# DAC_board_schematic.net
KiCad netlist of a schematic drawn in Altium Designer
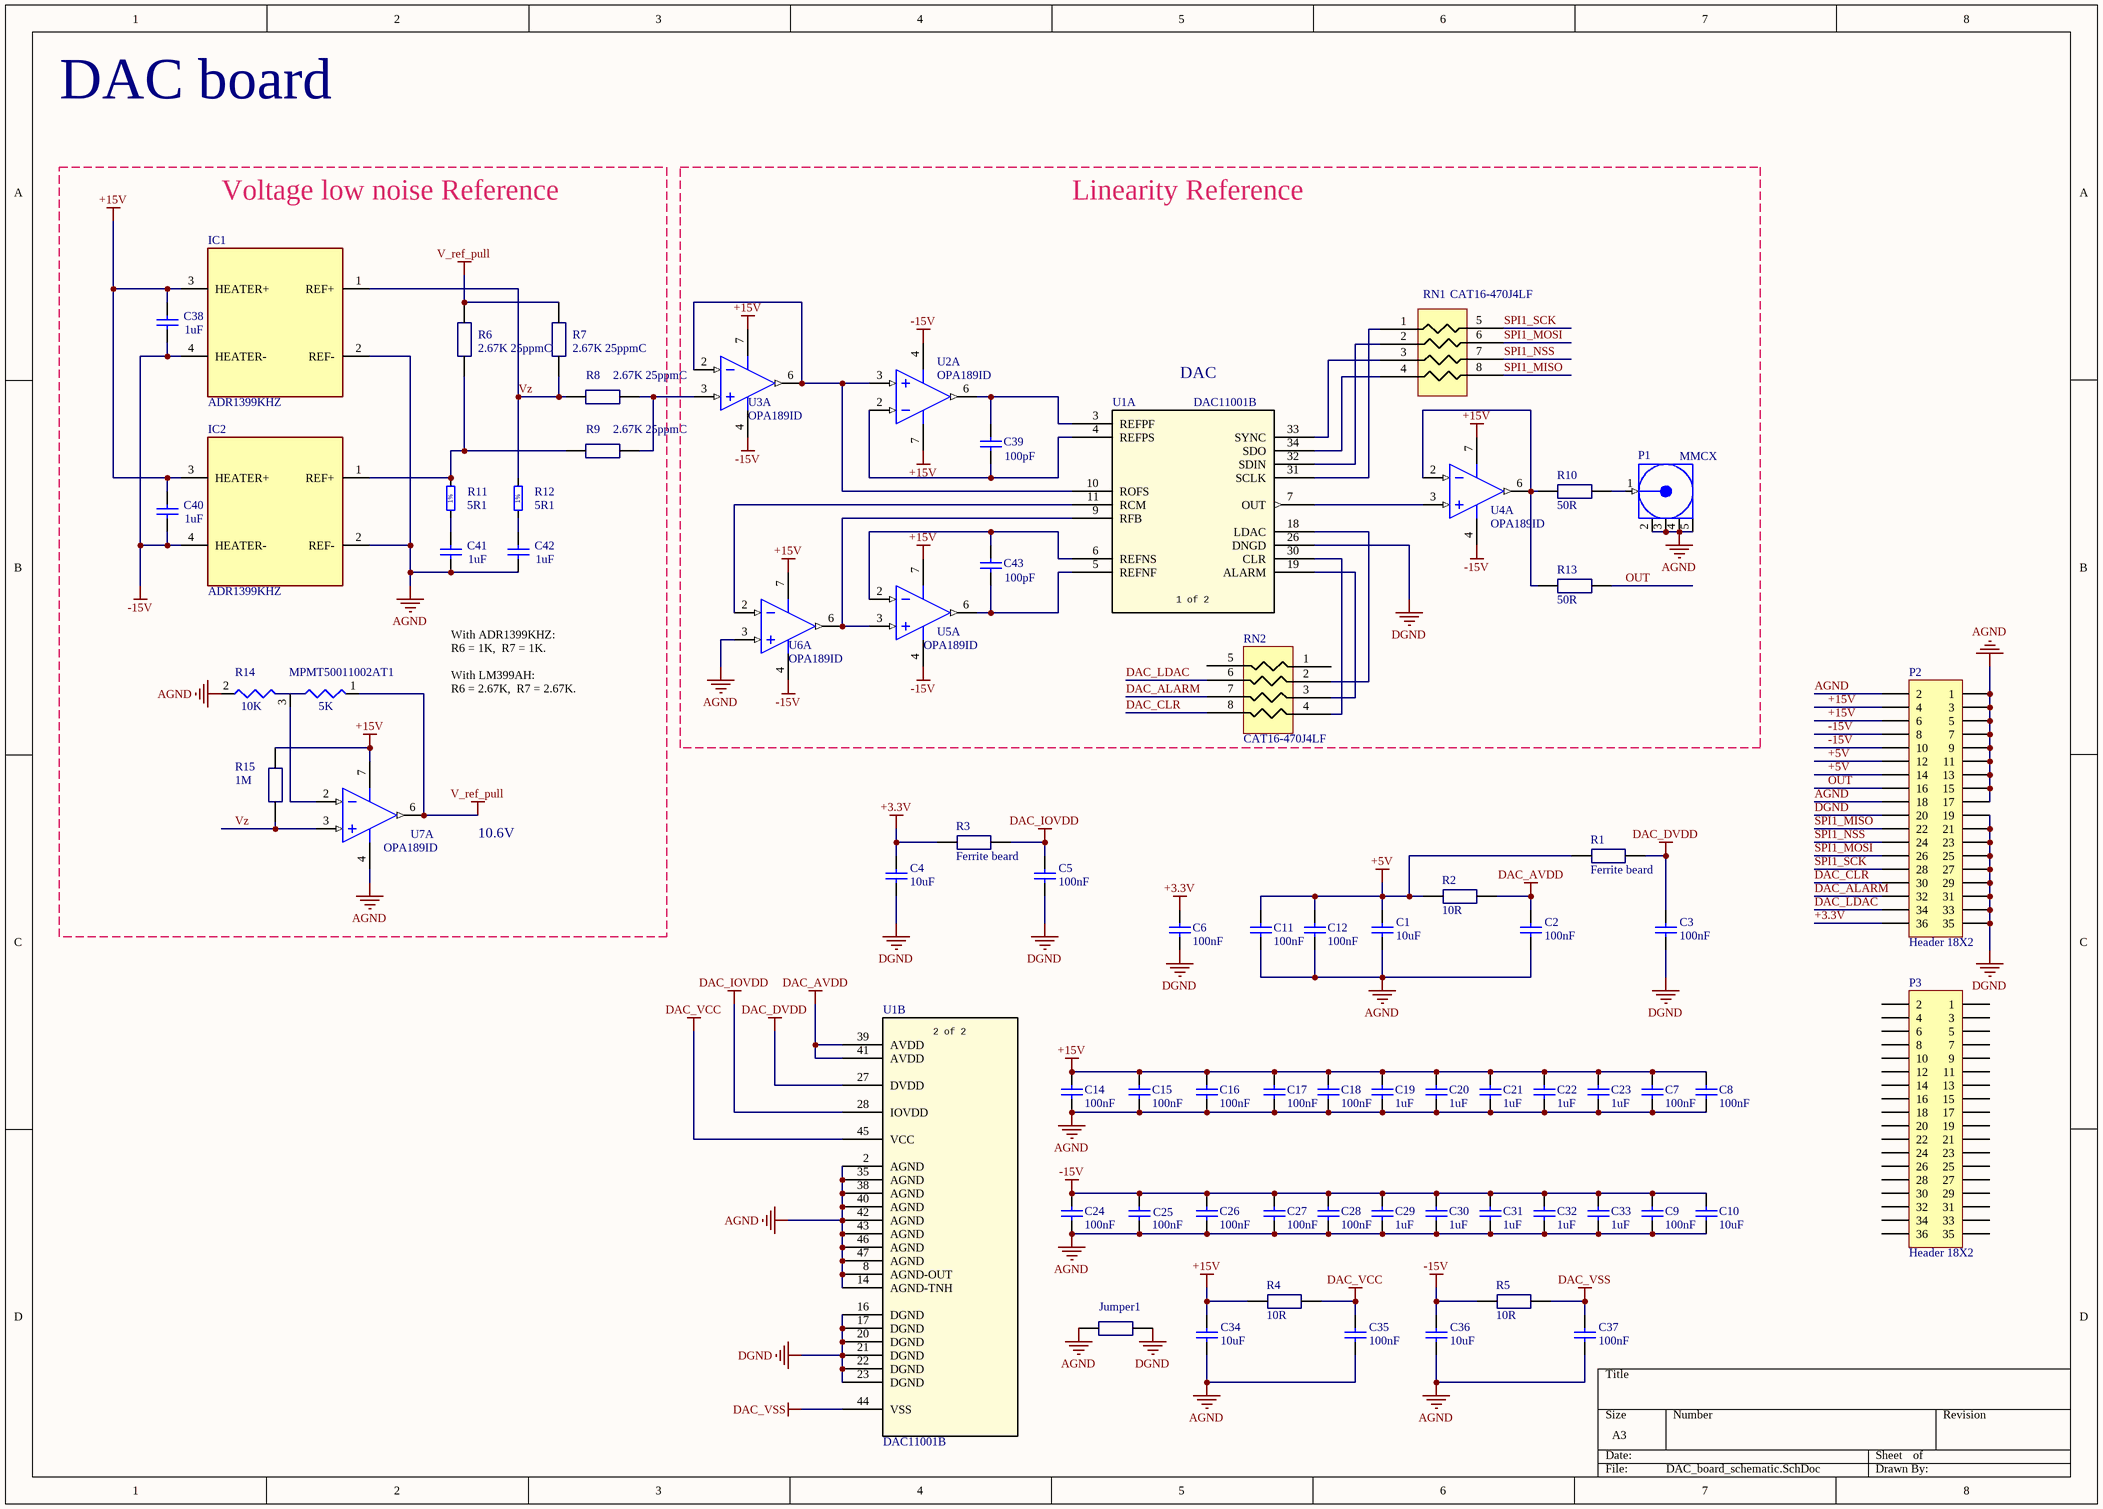
[diagram p0: DAC_board_schematic.SchDoc]

(export (version "E")
  (design (tool "Eeschema 10.0.6"))
  (components
    (comp (ref "C1")
      (value "10uF")
      (footprint "CAP 0603")
      (description "Capacitor (Semiconductor SIM Model)")
      (fields (field (name "PUBLISHER") "Altium Limited"))
      (libsource (lib "Miscellaneous Devices") (part "Cap Semi"))
    )
    (comp (ref "C2")
      (value "100nF")
      (footprint "CAP 0603")
      (description "Capacitor (Semiconductor SIM Model)")
      (fields (field (name "PUBLISHER") "Altium Limited"))
      (libsource (lib "Miscellaneous Devices") (part "Cap Semi"))
    )
    (comp (ref "C3")
      (value "100nF")
      (footprint "CAP 0603")
      (description "Capacitor (Semiconductor SIM Model)")
      (fields (field (name "PUBLISHER") "Altium Limited"))
      (libsource (lib "Miscellaneous Devices") (part "Cap Semi"))
    )
    (comp (ref "C4")
      (value "10uF")
      (footprint "CAP 0603")
      (description "Capacitor (Semiconductor SIM Model)")
      (fields (field (name "PUBLISHER") "Altium Limited"))
      (libsource (lib "Miscellaneous Devices") (part "Cap Semi"))
    )
    (comp (ref "C5")
      (value "100nF")
      (footprint "CAP 0603")
      (description "Capacitor (Semiconductor SIM Model)")
      (fields (field (name "PUBLISHER") "Altium Limited"))
      (libsource (lib "Miscellaneous Devices") (part "Cap Semi"))
    )
    (comp (ref "C6")
      (value "100nF")
      (footprint "CAP 0603")
      (description "Capacitor (Semiconductor SIM Model)")
      (fields (field (name "PUBLISHER") "Altium Limited"))
      (libsource (lib "Miscellaneous Devices") (part "Cap Semi"))
    )
    (comp (ref "C7")
      (value "100nF")
      (footprint "CAP 0603")
      (description "Capacitor (Semiconductor SIM Model)")
      (fields (field (name "PUBLISHER") "Altium Limited"))
      (libsource (lib "Miscellaneous Devices") (part "Cap Semi"))
    )
    (comp (ref "C8")
      (value "100nF")
      (footprint "CAP 0603")
      (description "Capacitor (Semiconductor SIM Model)")
      (fields (field (name "PUBLISHER") "Altium Limited"))
      (libsource (lib "Miscellaneous Devices") (part "Cap Semi"))
    )
    (comp (ref "C9")
      (value "100nF")
      (footprint "CAP 0603")
      (description "Capacitor (Semiconductor SIM Model)")
      (fields (field (name "PUBLISHER") "Altium Limited"))
      (libsource (lib "Miscellaneous Devices") (part "Cap Semi"))
    )
    (comp (ref "C10")
      (value "10uF")
      (footprint "CAP 0603")
      (description "Capacitor (Semiconductor SIM Model)")
      (fields (field (name "PUBLISHER") "Altium Limited"))
      (libsource (lib "Miscellaneous Devices") (part "Cap Semi"))
    )
    (comp (ref "C11")
      (value "100nF")
      (footprint "CAP 0603")
      (description "Capacitor (Semiconductor SIM Model)")
      (fields (field (name "PUBLISHER") "Altium Limited"))
      (libsource (lib "Miscellaneous Devices") (part "Cap Semi"))
    )
    (comp (ref "C12")
      (value "100nF")
      (footprint "CAP 0603")
      (description "Capacitor (Semiconductor SIM Model)")
      (fields (field (name "PUBLISHER") "Altium Limited"))
      (libsource (lib "Miscellaneous Devices") (part "Cap Semi"))
    )
    (comp (ref "C14")
      (value "100nF")
      (footprint "CAP 0603")
      (description "Capacitor (Semiconductor SIM Model)")
      (fields (field (name "PUBLISHER") "Altium Limited"))
      (libsource (lib "Miscellaneous Devices") (part "Cap Semi"))
    )
    (comp (ref "C15")
      (value "100nF")
      (footprint "CAP 0603")
      (description "Capacitor (Semiconductor SIM Model)")
      (fields (field (name "PUBLISHER") "Altium Limited"))
      (libsource (lib "Miscellaneous Devices") (part "Cap Semi"))
    )
    (comp (ref "C16")
      (value "100nF")
      (footprint "CAP 0603")
      (description "Capacitor (Semiconductor SIM Model)")
      (fields (field (name "PUBLISHER") "Altium Limited"))
      (libsource (lib "Miscellaneous Devices") (part "Cap Semi"))
    )
    (comp (ref "C17")
      (value "100nF")
      (footprint "CAP 0603")
      (description "Capacitor (Semiconductor SIM Model)")
      (fields (field (name "PUBLISHER") "Altium Limited"))
      (libsource (lib "Miscellaneous Devices") (part "Cap Semi"))
    )
    (comp (ref "C18")
      (value "100nF")
      (footprint "CAP 0603")
      (description "Capacitor (Semiconductor SIM Model)")
      (fields (field (name "PUBLISHER") "Altium Limited"))
      (libsource (lib "Miscellaneous Devices") (part "Cap Semi"))
    )
    (comp (ref "C19")
      (value "1uF")
      (footprint "CAP 0603")
      (description "Capacitor (Semiconductor SIM Model)")
      (fields (field (name "PUBLISHER") "Altium Limited"))
      (libsource (lib "Miscellaneous Devices") (part "Cap Semi"))
    )
    (comp (ref "C20")
      (value "1uF")
      (footprint "CAP 0603")
      (description "Capacitor (Semiconductor SIM Model)")
      (fields (field (name "PUBLISHER") "Altium Limited"))
      (libsource (lib "Miscellaneous Devices") (part "Cap Semi"))
    )
    (comp (ref "C21")
      (value "1uF")
      (footprint "CAP 0603")
      (description "Capacitor (Semiconductor SIM Model)")
      (fields (field (name "PUBLISHER") "Altium Limited"))
      (libsource (lib "Miscellaneous Devices") (part "Cap Semi"))
    )
    (comp (ref "C22")
      (value "1uF")
      (footprint "CAP 0603")
      (description "Capacitor (Semiconductor SIM Model)")
      (fields (field (name "PUBLISHER") "Altium Limited"))
      (libsource (lib "Miscellaneous Devices") (part "Cap Semi"))
    )
    (comp (ref "C23")
      (value "1uF")
      (footprint "CAP 0603")
      (description "Capacitor (Semiconductor SIM Model)")
      (fields (field (name "PUBLISHER") "Altium Limited"))
      (libsource (lib "Miscellaneous Devices") (part "Cap Semi"))
    )
    (comp (ref "C24")
      (value "100nF")
      (footprint "CAP 0603")
      (description "Capacitor (Semiconductor SIM Model)")
      (fields (field (name "PUBLISHER") "Altium Limited"))
      (libsource (lib "Miscellaneous Devices") (part "Cap Semi"))
    )
    (comp (ref "C25")
      (value "100nF")
      (footprint "CAP 0603")
      (description "Capacitor (Semiconductor SIM Model)")
      (fields (field (name "PUBLISHER") "Altium Limited"))
      (libsource (lib "Miscellaneous Devices") (part "Cap Semi"))
    )
    (comp (ref "C26")
      (value "100nF")
      (footprint "CAP 0603")
      (description "Capacitor (Semiconductor SIM Model)")
      (fields (field (name "PUBLISHER") "Altium Limited"))
      (libsource (lib "Miscellaneous Devices") (part "Cap Semi"))
    )
    (comp (ref "C27")
      (value "100nF")
      (footprint "CAP 0603")
      (description "Capacitor (Semiconductor SIM Model)")
      (fields (field (name "PUBLISHER") "Altium Limited"))
      (libsource (lib "Miscellaneous Devices") (part "Cap Semi"))
    )
    (comp (ref "C28")
      (value "100nF")
      (footprint "CAP 0603")
      (description "Capacitor (Semiconductor SIM Model)")
      (fields (field (name "PUBLISHER") "Altium Limited"))
      (libsource (lib "Miscellaneous Devices") (part "Cap Semi"))
    )
    (comp (ref "C29")
      (value "1uF")
      (footprint "CAP 0603")
      (description "Capacitor (Semiconductor SIM Model)")
      (fields (field (name "PUBLISHER") "Altium Limited"))
      (libsource (lib "Miscellaneous Devices") (part "Cap Semi"))
    )
    (comp (ref "C30")
      (value "1uF")
      (footprint "CAP 0603")
      (description "Capacitor (Semiconductor SIM Model)")
      (fields (field (name "PUBLISHER") "Altium Limited"))
      (libsource (lib "Miscellaneous Devices") (part "Cap Semi"))
    )
    (comp (ref "C31")
      (value "1uF")
      (footprint "CAP 0603")
      (description "Capacitor (Semiconductor SIM Model)")
      (fields (field (name "PUBLISHER") "Altium Limited"))
      (libsource (lib "Miscellaneous Devices") (part "Cap Semi"))
    )
    (comp (ref "C32")
      (value "1uF")
      (footprint "CAP 0603")
      (description "Capacitor (Semiconductor SIM Model)")
      (fields (field (name "PUBLISHER") "Altium Limited"))
      (libsource (lib "Miscellaneous Devices") (part "Cap Semi"))
    )
    (comp (ref "C33")
      (value "1uF")
      (footprint "CAP 0603")
      (description "Capacitor (Semiconductor SIM Model)")
      (fields (field (name "PUBLISHER") "Altium Limited"))
      (libsource (lib "Miscellaneous Devices") (part "Cap Semi"))
    )
    (comp (ref "C34")
      (value "10uF")
      (footprint "C1206")
      (description "Capacitor (Semiconductor SIM Model)")
      (fields (field (name "PUBLISHER") "Altium Limited"))
      (libsource (lib "Miscellaneous Devices") (part "Cap Semi"))
    )
    (comp (ref "C35")
      (value "100nF")
      (footprint "CAP 0603")
      (description "Capacitor (Semiconductor SIM Model)")
      (fields (field (name "PUBLISHER") "Altium Limited"))
      (libsource (lib "Miscellaneous Devices") (part "Cap Semi"))
    )
    (comp (ref "C36")
      (value "10uF")
      (footprint "C1206")
      (description "Capacitor (Semiconductor SIM Model)")
      (fields (field (name "PUBLISHER") "Altium Limited"))
      (libsource (lib "Miscellaneous Devices") (part "Cap Semi"))
    )
    (comp (ref "C37")
      (value "100nF")
      (footprint "CAP 0603")
      (description "Capacitor (Semiconductor SIM Model)")
      (fields (field (name "PUBLISHER") "Altium Limited"))
      (libsource (lib "Miscellaneous Devices") (part "Cap Semi"))
    )
    (comp (ref "C38")
      (value "1uF")
      (footprint "CAPC3216X140N")
      (description "Non-polarised capacitor")
      (fields
        (field (name "PART NUMBER") "CC1206_1UF_25V_10%_X7R")
        (field (name "VOLTAGE") "25V")
        (field (name "AUTHOR") "CERN DEM JLC")
      )
      (libsource (lib "Capacitors") (part "Capacitor - non polarized"))
    )
    (comp (ref "C39")
      (value "100pF")
      (footprint "0402")
      (description "Capacitor (Semiconductor SIM Model)")
      (fields (field (name "Comment") "Cap Semi") (field (name "PUBLISHER") "Altium Limited"))
      (libsource (lib "Miscellaneous Devices") (part "Cap Semi"))
    )
    (comp (ref "C40")
      (value "1uF")
      (footprint "CAPC3216X140N")
      (description "Non-polarised capacitor")
      (fields
        (field (name "PART NUMBER") "CC1206_1UF_25V_10%_X7R")
        (field (name "VOLTAGE") "25V")
        (field (name "AUTHOR") "CERN DEM JLC")
      )
      (libsource (lib "Capacitors") (part "Capacitor - non polarized"))
    )
    (comp (ref "C41")
      (value "1uF")
      (footprint "CAPC3216X140N")
      (description "Non-polarised capacitor")
      (fields
        (field (name "PART NUMBER") "CC1206_1UF_25V_10%_X7R")
        (field (name "VOLTAGE") "25V")
        (field (name "AUTHOR") "CERN DEM JLC")
      )
      (libsource (lib "Capacitors") (part "Capacitor - non polarized"))
    )
    (comp (ref "C42")
      (value "1uF")
      (footprint "CAPC3216X140N")
      (description "Non-polarised capacitor")
      (fields
        (field (name "PART NUMBER") "CC1206_1UF_25V_10%_X7R")
        (field (name "VOLTAGE") "25V")
        (field (name "AUTHOR") "CERN DEM JLC")
      )
      (libsource (lib "Capacitors") (part "Capacitor - non polarized"))
    )
    (comp (ref "C43")
      (value "100pF")
      (footprint "0402")
      (description "Capacitor (Semiconductor SIM Model)")
      (fields (field (name "Comment") "Cap Semi") (field (name "PUBLISHER") "Altium Limited"))
      (libsource (lib "Miscellaneous Devices") (part "Cap Semi"))
    )
    (comp (ref "IC1")
      (value "ADR1399KHZ")
      (footprint "SamacSys:ADR1399KHZ")
      (description "Integrated Circuit")
      (libsource (lib "SamacSys") (part "ADR1399KHZ"))
    )
    (comp (ref "IC2")
      (value "ADR1399KHZ")
      (footprint "SamacSys:ADR1399KHZ")
      (description "Integrated Circuit")
      (libsource (lib "SamacSys") (part "ADR1399KHZ"))
    )
    (comp (ref "Jumper1")
      (value "~")
      (footprint "0402 jumper")
      (libsource (lib "Микрон-3") (part "Resistor 0805"))
    )
    (comp (ref "P1")
      (value "MMCX")
      (footprint "MMCX2.54-V5")
      (description "RF Coaxial PCB Connector, MMCX; Thru-Hole, Vertical Mount Plug,  50 Ohm Impedance")
      (fields (field (name "PUBLISHER") "Altium Limited"))
      (libsource (lib "Miscellaneous Connectors") (part "COAX-M"))
    )
    (comp (ref "P2")
      (value "Header 18X2")
      (footprint "HDR2X18")
      (description "Header, 18-Pin, Dual row")
      (fields (field (name "PUBLISHER") "Altium Limited"))
      (libsource (lib "Miscellaneous Connectors") (part "Header 18X2"))
    )
    (comp (ref "P3")
      (value "Header 18X2")
      (footprint "HDR2X18")
      (description "Header, 18-Pin, Dual row")
      (fields (field (name "PUBLISHER") "Altium Limited"))
      (libsource (lib "Miscellaneous Connectors") (part "Header 18X2"))
    )
    (comp (ref "R1")
      (value "Ferrite beard")
      (footprint "CC1206JRNPOBBN100")
      (libsource (lib "Микрон-3") (part "Resistor 0805"))
    )
    (comp (ref "R2")
      (value "10R")
      (footprint "1608[0603]")
      (libsource (lib "Микрон-3") (part "Resistor 0805"))
    )
    (comp (ref "R3")
      (value "Ferrite beard")
      (footprint "CC1206JRNPOBBN100")
      (libsource (lib "Микрон-3") (part "Resistor 0805"))
    )
    (comp (ref "R4")
      (value "10R")
      (footprint "1608[0603]")
      (libsource (lib "Микрон-3") (part "Resistor 0805"))
    )
    (comp (ref "R5")
      (value "10R")
      (footprint "1608[0603]")
      (libsource (lib "Микрон-3") (part "Resistor 0805"))
    )
    (comp (ref "R6")
      (value "2.67K 25ppmC")
      (footprint "1608[0603]")
      (libsource (lib "Микрон-3") (part "Resistor 0805"))
    )
    (comp (ref "R7")
      (value "2.67K 25ppmC")
      (footprint "1608[0603]")
      (libsource (lib "Микрон-3") (part "Resistor 0805"))
    )
    (comp (ref "R8")
      (value "2.67K 25ppmC")
      (footprint "1608[0603]")
      (libsource (lib "Микрон-3") (part "Resistor 0805"))
    )
    (comp (ref "R9")
      (value "2.67K 25ppmC")
      (footprint "1608[0603]")
      (libsource (lib "Микрон-3") (part "Resistor 0805"))
    )
    (comp (ref "R10")
      (value "50R")
      (footprint "1608[0603]")
      (libsource (lib "Микрон-3") (part "Resistor 0805"))
    )
    (comp (ref "R11")
      (value "5R1")
      (footprint "RESC3216X65N")
      (description "Resistor - 1%")
      (fields
        (field (name "PART NUMBER") "R1206_5R6_1%_0.25W_200PPM")
        (field (name "POWER") "0.25W")
        (field (name "AUTHOR") "CERN DEM JLC")
      )
      (libsource (lib "Resistors") (part "Resistor - 1%"))
    )
    (comp (ref "R12")
      (value "5R1")
      (footprint "RESC3216X65N")
      (description "Resistor - 1%")
      (fields
        (field (name "PART NUMBER") "R1206_5R6_1%_0.25W_200PPM")
        (field (name "POWER") "0.25W")
        (field (name "AUTHOR") "CERN DEM JLC")
      )
      (libsource (lib "Resistors") (part "Resistor - 1%"))
    )
    (comp (ref "R13")
      (value "50R")
      (footprint "1608[0603]")
      (libsource (lib "Микрон-3") (part "Resistor 0805"))
    )
    (comp (ref "R14")
      (value "5K")
      (footprint "SOT23-3")
      (fields
        (field (name "VALUE2") "10K")
        (field (name "ORDER") "MPMT50011002AT1")
        (field (name "Comment") "MPMT50011002AT1")
        (field (name "PUBLISHER") "Altium Limited")
      )
      (libsource (lib "My SCH library") (part "MPMT"))
    )
    (comp (ref "R15")
      (value "1M")
      (footprint "1608[0603]")
      (libsource (lib "Микрон-3") (part "Resistor 0805"))
    )
    (comp (ref "RN1")
      (value "CAT16-470J4LF")
      (footprint "CAT16-470J4LF")
      (libsource (lib "My SCH library") (part "CAT16-470J4LF"))
    )
    (comp (ref "RN2")
      (value "CAT16-470J4LF")
      (footprint "CAT16-470J4LF")
      (libsource (lib "") (part "CAT16-470J4LF_1"))
    )
    (comp (ref "U1")
      (value "DAC11001B")
      (footprint "QFP_APFBR_TEX")
      (description "No Description Available")
      (fields
        (field (name "MANUFACTURER_PART_NUMBER") "DAC11001APFBR")
        (field (name "COPYRIGHT") "Copyright (C) 2018 Accelerated Designs. All rights reserved")
      )
      (libsource (lib "Ramp-generator") (part "DAC11001APFBR"))
    )
    (comp (ref "U2")
      (value "OPA189ID")
      (footprint "TI-D8_L")
      (fields (field (name "MANUFACTURER") "Texas Instruments"))
      (libsource (lib "") (part "OPA140AIDR_1"))
    )
    (comp (ref "U3")
      (value "OPA189ID")
      (footprint "TI-D8_L")
      (fields (field (name "MANUFACTURER") "Texas Instruments"))
      (libsource (lib "TI Amplifiers and Linear Operational Amplifier Precision Amplifier Part One") (part "OPA140AIDR"))
    )
    (comp (ref "U4")
      (value "OPA189ID")
      (footprint "TI-D8_L")
      (fields (field (name "MANUFACTURER") "Texas Instruments"))
      (libsource (lib "TI Amplifiers and Linear Operational Amplifier Precision Amplifier Part One") (part "OPA140AIDR"))
    )
    (comp (ref "U5")
      (value "OPA189ID")
      (footprint "TI-D8_L")
      (fields (field (name "MANUFACTURER") "Texas Instruments"))
      (libsource (lib "TI Amplifiers and Linear Operational Amplifier Precision Amplifier Part One") (part "OPA140AIDR"))
    )
    (comp (ref "U6")
      (value "OPA189ID")
      (footprint "TI-D8_L")
      (fields (field (name "MANUFACTURER") "Texas Instruments"))
      (libsource (lib "TI Amplifiers and Linear Operational Amplifier Precision Amplifier Part One") (part "OPA140AIDR"))
    )
    (comp (ref "U7")
      (value "OPA189ID")
      (footprint "TI-D8_L")
      (fields (field (name "MANUFACTURER") "Texas Instruments"))
      (libsource (lib "TI Amplifiers and Linear Operational Amplifier Precision Amplifier Part One") (part "OPA140AIDR"))
    )
  )
  (nets
    (net (code "1") (name "+3.3V") (class "Default")
      (node (ref "C4") (pin "1") (pinfunction "1_1") (pintype "passive"))
      (node (ref "C6") (pin "2") (pinfunction "2_2") (pintype "passive"))
      (node (ref "P2") (pin "36") (pinfunction "36_36") (pintype "passive"))
      (node (ref "R3") (pin "2") (pinfunction "2_2") (pintype "passive"))
    )
    (net (code "2") (name "+5V") (class "Default")
      (node (ref "C1") (pin "1") (pinfunction "1_1") (pintype "passive"))
      (node (ref "C11") (pin "2") (pinfunction "2_2") (pintype "passive"))
      (node (ref "C12") (pin "2") (pinfunction "2_2") (pintype "passive"))
      (node (ref "P2") (pin "12") (pinfunction "12_12") (pintype "passive"))
      (node (ref "P2") (pin "14") (pinfunction "14_14") (pintype "passive"))
      (node (ref "R1") (pin "2") (pinfunction "2_2") (pintype "passive"))
      (node (ref "R2") (pin "2") (pinfunction "2_2") (pintype "passive"))
    )
    (net (code "3") (name "+15V") (class "Default")
      (node (ref "C14") (pin "2") (pinfunction "2_2") (pintype "passive"))
      (node (ref "C15") (pin "2") (pinfunction "2_2") (pintype "passive"))
      (node (ref "C16") (pin "2") (pinfunction "2_2") (pintype "passive"))
      (node (ref "C17") (pin "2") (pinfunction "2_2") (pintype "passive"))
      (node (ref "C18") (pin "2") (pinfunction "2_2") (pintype "passive"))
      (node (ref "C19") (pin "2") (pinfunction "2_2") (pintype "passive"))
      (node (ref "C20") (pin "2") (pinfunction "2_2") (pintype "passive"))
      (node (ref "C21") (pin "2") (pinfunction "2_2") (pintype "passive"))
      (node (ref "C22") (pin "2") (pinfunction "2_2") (pintype "passive"))
      (node (ref "C23") (pin "2") (pinfunction "2_2") (pintype "passive"))
      (node (ref "C34") (pin "1") (pinfunction "1_1") (pintype "passive"))
      (node (ref "C38") (pin "2") (pinfunction "2_2") (pintype "passive"))
      (node (ref "C40") (pin "2") (pinfunction "2_2") (pintype "passive"))
      (node (ref "C7") (pin "2") (pinfunction "2_2") (pintype "passive"))
      (node (ref "C8") (pin "2") (pinfunction "2_2") (pintype "passive"))
      (node (ref "IC1") (pin "3") (pinfunction "HEATER+_3") (pintype "passive"))
      (node (ref "IC2") (pin "3") (pinfunction "HEATER+_3") (pintype "passive"))
      (node (ref "P2") (pin "4") (pinfunction "4_4") (pintype "passive"))
      (node (ref "P2") (pin "6") (pinfunction "6_6") (pintype "passive"))
      (node (ref "R15") (pin "1") (pinfunction "A_1") (pintype "passive"))
      (node (ref "R4") (pin "2") (pinfunction "2_2") (pintype "passive"))
      (node (ref "U2") (pin "7") (pinfunction "V+_7") (pintype "power_in"))
      (node (ref "U3") (pin "7") (pinfunction "V+_7") (pintype "power_in"))
      (node (ref "U4") (pin "7") (pinfunction "V+_7") (pintype "power_in"))
      (node (ref "U5") (pin "7") (pinfunction "V+_7") (pintype "power_in"))
      (node (ref "U6") (pin "7") (pinfunction "V+_7") (pintype "power_in"))
      (node (ref "U7") (pin "7") (pinfunction "V+_7") (pintype "power_in"))
    )
    (net (code "4") (name "-15V") (class "Default")
      (node (ref "C10") (pin "2") (pinfunction "2_2") (pintype "passive"))
      (node (ref "C24") (pin "2") (pinfunction "2_2") (pintype "passive"))
      (node (ref "C25") (pin "2") (pinfunction "2_2") (pintype "passive"))
      (node (ref "C26") (pin "2") (pinfunction "2_2") (pintype "passive"))
      (node (ref "C27") (pin "2") (pinfunction "2_2") (pintype "passive"))
      (node (ref "C28") (pin "2") (pinfunction "2_2") (pintype "passive"))
      (node (ref "C29") (pin "2") (pinfunction "2_2") (pintype "passive"))
      (node (ref "C30") (pin "2") (pinfunction "2_2") (pintype "passive"))
      (node (ref "C31") (pin "2") (pinfunction "2_2") (pintype "passive"))
      (node (ref "C32") (pin "2") (pinfunction "2_2") (pintype "passive"))
      (node (ref "C33") (pin "2") (pinfunction "2_2") (pintype "passive"))
      (node (ref "C36") (pin "1") (pinfunction "1_1") (pintype "passive"))
      (node (ref "C38") (pin "1") (pinfunction "1_1") (pintype "passive"))
      (node (ref "C40") (pin "1") (pinfunction "1_1") (pintype "passive"))
      (node (ref "C9") (pin "2") (pinfunction "2_2") (pintype "passive"))
      (node (ref "IC1") (pin "4") (pinfunction "HEATER-_4") (pintype "passive"))
      (node (ref "IC2") (pin "4") (pinfunction "HEATER-_4") (pintype "passive"))
      (node (ref "P2") (pin "10") (pinfunction "10_10") (pintype "passive"))
      (node (ref "P2") (pin "8") (pinfunction "8_8") (pintype "passive"))
      (node (ref "R5") (pin "2") (pinfunction "2_2") (pintype "passive"))
      (node (ref "U2") (pin "4") (pinfunction "V-_4") (pintype "power_in"))
      (node (ref "U3") (pin "4") (pinfunction "V-_4") (pintype "power_in"))
      (node (ref "U4") (pin "4") (pinfunction "V-_4") (pintype "power_in"))
      (node (ref "U5") (pin "4") (pinfunction "V-_4") (pintype "power_in"))
      (node (ref "U6") (pin "4") (pinfunction "V-_4") (pintype "power_in"))
    )
    (net (code "5") (name "/DAC_ALARM") (class "Default")
      (node (ref "P2") (pin "32") (pinfunction "32_32") (pintype "passive"))
      (node (ref "RN2") (pin "7") (pinfunction "7_7") (pintype "passive"))
    )
    (net (code "6") (name "/DAC_CLR") (class "Default")
      (node (ref "P2") (pin "30") (pinfunction "30_30") (pintype "passive"))
      (node (ref "RN2") (pin "8") (pinfunction "8_8") (pintype "passive"))
    )
    (net (code "7") (name "/DAC_LDAC") (class "Default")
      (node (ref "P2") (pin "34") (pinfunction "34_34") (pintype "passive"))
      (node (ref "RN2") (pin "6") (pinfunction "6_6") (pintype "passive"))
    )
    (net (code "8") (name "/OUT") (class "Default")
      (node (ref "P2") (pin "16") (pinfunction "16_16") (pintype "passive"))
      (node (ref "R13") (pin "1") (pinfunction "A_1") (pintype "passive"))
    )
    (net (code "9") (name "/SPI1_MISO") (class "Default")
      (node (ref "P2") (pin "22") (pinfunction "22_22") (pintype "passive"))
      (node (ref "RN1") (pin "8") (pinfunction "8_8") (pintype "passive"))
    )
    (net (code "10") (name "/SPI1_MOSI") (class "Default")
      (node (ref "P2") (pin "26") (pinfunction "26_26") (pintype "passive"))
      (node (ref "RN1") (pin "6") (pinfunction "6_6") (pintype "passive"))
    )
    (net (code "11") (name "/SPI1_NSS") (class "Default")
      (node (ref "P2") (pin "24") (pinfunction "24_24") (pintype "passive"))
      (node (ref "RN1") (pin "7") (pinfunction "7_7") (pintype "passive"))
    )
    (net (code "12") (name "/SPI1_SCK") (class "Default")
      (node (ref "P2") (pin "28") (pinfunction "28_28") (pintype "passive"))
      (node (ref "RN1") (pin "5") (pinfunction "5_5") (pintype "passive"))
    )
    (net (code "13") (name "/Vz") (class "Default")
      (node (ref "IC1") (pin "1") (pinfunction "REF+_1") (pintype "passive"))
      (node (ref "R12") (pin "2") (pinfunction "2_2") (pintype "passive"))
      (node (ref "R15") (pin "2") (pinfunction "2_2") (pintype "passive"))
      (node (ref "R7") (pin "2") (pinfunction "2_2") (pintype "passive"))
      (node (ref "R8") (pin "2") (pinfunction "2_2") (pintype "passive"))
      (node (ref "U7") (pin "3") (pinfunction "IN+_3") (pintype "input"))
    )
    (net (code "14") (name "AGND") (class "Default")
      (node (ref "C1") (pin "2") (pinfunction "2_2") (pintype "passive"))
      (node (ref "C10") (pin "1") (pinfunction "1_1") (pintype "passive"))
      (node (ref "C11") (pin "1") (pinfunction "1_1") (pintype "passive"))
      (node (ref "C12") (pin "1") (pinfunction "1_1") (pintype "passive"))
      (node (ref "C14") (pin "1") (pinfunction "1_1") (pintype "passive"))
      (node (ref "C15") (pin "1") (pinfunction "1_1") (pintype "passive"))
      (node (ref "C16") (pin "1") (pinfunction "1_1") (pintype "passive"))
      (node (ref "C17") (pin "1") (pinfunction "1_1") (pintype "passive"))
      (node (ref "C18") (pin "1") (pinfunction "1_1") (pintype "passive"))
      (node (ref "C19") (pin "1") (pinfunction "1_1") (pintype "passive"))
      (node (ref "C2") (pin "2") (pinfunction "2_2") (pintype "passive"))
      (node (ref "C20") (pin "1") (pinfunction "1_1") (pintype "passive"))
      (node (ref "C21") (pin "1") (pinfunction "1_1") (pintype "passive"))
      (node (ref "C22") (pin "1") (pinfunction "1_1") (pintype "passive"))
      (node (ref "C23") (pin "1") (pinfunction "1_1") (pintype "passive"))
      (node (ref "C24") (pin "1") (pinfunction "1_1") (pintype "passive"))
      (node (ref "C25") (pin "1") (pinfunction "1_1") (pintype "passive"))
      (node (ref "C26") (pin "1") (pinfunction "1_1") (pintype "passive"))
      (node (ref "C27") (pin "1") (pinfunction "1_1") (pintype "passive"))
      (node (ref "C28") (pin "1") (pinfunction "1_1") (pintype "passive"))
      (node (ref "C29") (pin "1") (pinfunction "1_1") (pintype "passive"))
      (node (ref "C30") (pin "1") (pinfunction "1_1") (pintype "passive"))
      (node (ref "C31") (pin "1") (pinfunction "1_1") (pintype "passive"))
      (node (ref "C32") (pin "1") (pinfunction "1_1") (pintype "passive"))
      (node (ref "C33") (pin "1") (pinfunction "1_1") (pintype "passive"))
      (node (ref "C34") (pin "2") (pinfunction "2_2") (pintype "passive"))
      (node (ref "C35") (pin "2") (pinfunction "2_2") (pintype "passive"))
      (node (ref "C36") (pin "2") (pinfunction "2_2") (pintype "passive"))
      (node (ref "C37") (pin "2") (pinfunction "2_2") (pintype "passive"))
      (node (ref "C41") (pin "1") (pinfunction "1_1") (pintype "passive"))
      (node (ref "C42") (pin "1") (pinfunction "1_1") (pintype "passive"))
      (node (ref "C7") (pin "1") (pinfunction "1_1") (pintype "passive"))
      (node (ref "C8") (pin "1") (pinfunction "1_1") (pintype "passive"))
      (node (ref "C9") (pin "1") (pinfunction "1_1") (pintype "passive"))
      (node (ref "IC1") (pin "2") (pinfunction "REF-_2") (pintype "passive"))
      (node (ref "IC2") (pin "2") (pinfunction "REF-_2") (pintype "passive"))
      (node (ref "Jumper1") (pin "2") (pinfunction "2_2") (pintype "passive"))
      (node (ref "P1") (pin "2") (pinfunction "GND_2") (pintype "power_in"))
      (node (ref "P1") (pin "3") (pinfunction "GND_3") (pintype "power_in"))
      (node (ref "P1") (pin "4") (pinfunction "GND_4") (pintype "power_in"))
      (node (ref "P1") (pin "5") (pinfunction "GND_5") (pintype "power_in"))
      (node (ref "P2") (pin "1") (pinfunction "1_1") (pintype "passive"))
      (node (ref "P2") (pin "11") (pinfunction "11_11") (pintype "passive"))
      (node (ref "P2") (pin "13") (pinfunction "13_13") (pintype "passive"))
      (node (ref "P2") (pin "15") (pinfunction "15_15") (pintype "passive"))
      (node (ref "P2") (pin "17") (pinfunction "17_17") (pintype "passive"))
      (node (ref "P2") (pin "18") (pinfunction "18_18") (pintype "passive"))
      (node (ref "P2") (pin "2") (pinfunction "2_2") (pintype "passive"))
      (node (ref "P2") (pin "3") (pinfunction "3_3") (pintype "passive"))
      (node (ref "P2") (pin "5") (pinfunction "5_5") (pintype "passive"))
      (node (ref "P2") (pin "7") (pinfunction "7_7") (pintype "passive"))
      (node (ref "P2") (pin "9") (pinfunction "9_9") (pintype "passive"))
      (node (ref "R14") (pin "2") (pinfunction "2_2") (pintype "passive"))
      (node (ref "U1") (pin "14") (pinfunction "AGND-TNH_14") (pintype "passive"))
      (node (ref "U1") (pin "2") (pinfunction "AGND_2") (pintype "passive"))
      (node (ref "U1") (pin "35") (pinfunction "AGND_35") (pintype "passive"))
      (node (ref "U1") (pin "38") (pinfunction "AGND_38") (pintype "passive"))
      (node (ref "U1") (pin "40") (pinfunction "AGND_40") (pintype "passive"))
      (node (ref "U1") (pin "42") (pinfunction "AGND_42") (pintype "passive"))
      (node (ref "U1") (pin "43") (pinfunction "AGND_43") (pintype "passive"))
      (node (ref "U1") (pin "46") (pinfunction "AGND_46") (pintype "passive"))
      (node (ref "U1") (pin "47") (pinfunction "AGND_47") (pintype "passive"))
      (node (ref "U1") (pin "8") (pinfunction "AGND-OUT_8") (pintype "passive"))
      (node (ref "U6") (pin "3") (pinfunction "IN+_3") (pintype "input"))
      (node (ref "U7") (pin "4") (pinfunction "V-_4") (pintype "power_in"))
    )
    (net (code "15") (name "DAC_AVDD") (class "Default")
      (node (ref "C2") (pin "1") (pinfunction "1_1") (pintype "passive"))
      (node (ref "R2") (pin "1") (pinfunction "A_1") (pintype "passive"))
      (node (ref "U1") (pin "39") (pinfunction "AVDD_39") (pintype "power_in"))
      (node (ref "U1") (pin "41") (pinfunction "AVDD_41") (pintype "power_in"))
    )
    (net (code "16") (name "DAC_DVDD") (class "Default")
      (node (ref "C3") (pin "1") (pinfunction "1_1") (pintype "passive"))
      (node (ref "R1") (pin "1") (pinfunction "A_1") (pintype "passive"))
      (node (ref "U1") (pin "27") (pinfunction "DVDD_27") (pintype "power_in"))
    )
    (net (code "17") (name "DAC_IOVDD") (class "Default")
      (node (ref "C5") (pin "1") (pinfunction "1_1") (pintype "passive"))
      (node (ref "R3") (pin "1") (pinfunction "A_1") (pintype "passive"))
      (node (ref "U1") (pin "28") (pinfunction "IOVDD_28") (pintype "power_in"))
    )
    (net (code "18") (name "DAC_VCC") (class "Default")
      (node (ref "C35") (pin "1") (pinfunction "1_1") (pintype "passive"))
      (node (ref "R4") (pin "1") (pinfunction "A_1") (pintype "passive"))
      (node (ref "U1") (pin "45") (pinfunction "VCC_45") (pintype "power_in"))
    )
    (net (code "19") (name "DAC_VSS") (class "Default")
      (node (ref "C37") (pin "1") (pinfunction "1_1") (pintype "passive"))
      (node (ref "R5") (pin "1") (pinfunction "A_1") (pintype "passive"))
      (node (ref "U1") (pin "44") (pinfunction "VSS_44") (pintype "passive"))
    )
    (net (code "20") (name "DGND") (class "Default")
      (node (ref "C3") (pin "2") (pinfunction "2_2") (pintype "passive"))
      (node (ref "C4") (pin "2") (pinfunction "2_2") (pintype "passive"))
      (node (ref "C5") (pin "2") (pinfunction "2_2") (pintype "passive"))
      (node (ref "C6") (pin "1") (pinfunction "1_1") (pintype "passive"))
      (node (ref "Jumper1") (pin "1") (pinfunction "A_1") (pintype "passive"))
      (node (ref "P2") (pin "19") (pinfunction "19_19") (pintype "passive"))
      (node (ref "P2") (pin "20") (pinfunction "20_20") (pintype "passive"))
      (node (ref "P2") (pin "21") (pinfunction "21_21") (pintype "passive"))
      (node (ref "P2") (pin "23") (pinfunction "23_23") (pintype "passive"))
      (node (ref "P2") (pin "25") (pinfunction "25_25") (pintype "passive"))
      (node (ref "P2") (pin "27") (pinfunction "27_27") (pintype "passive"))
      (node (ref "P2") (pin "29") (pinfunction "29_29") (pintype "passive"))
      (node (ref "P2") (pin "31") (pinfunction "31_31") (pintype "passive"))
      (node (ref "P2") (pin "33") (pinfunction "33_33") (pintype "passive"))
      (node (ref "P2") (pin "35") (pinfunction "35_35") (pintype "passive"))
      (node (ref "U1") (pin "16") (pinfunction "DGND_16") (pintype "passive"))
      (node (ref "U1") (pin "17") (pinfunction "DGND_17") (pintype "passive"))
      (node (ref "U1") (pin "20") (pinfunction "DGND_20") (pintype "passive"))
      (node (ref "U1") (pin "21") (pinfunction "DGND_21") (pintype "passive"))
      (node (ref "U1") (pin "22") (pinfunction "DGND_22") (pintype "passive"))
      (node (ref "U1") (pin "23") (pinfunction "DGND_23") (pintype "passive"))
      (node (ref "U1") (pin "26") (pinfunction "DNGD_26") (pintype "passive"))
    )
    (net (code "21") (name "Net-(C41-Pad2)") (class "Default")
      (node (ref "C41") (pin "2") (pinfunction "2_2") (pintype "passive"))
      (node (ref "R11") (pin "1") (pinfunction "1_1") (pintype "passive"))
    )
    (net (code "22") (name "Net-(C42-Pad2)") (class "Default")
      (node (ref "C42") (pin "2") (pinfunction "2_2") (pintype "passive"))
      (node (ref "R12") (pin "1") (pinfunction "1_1") (pintype "passive"))
    )
    (net (code "23") (name "Net-(IC2-REF+)") (class "Default")
      (node (ref "IC2") (pin "1") (pinfunction "REF+_1") (pintype "passive"))
      (node (ref "R11") (pin "2") (pinfunction "2_2") (pintype "passive"))
      (node (ref "R6") (pin "2") (pinfunction "2_2") (pintype "passive"))
      (node (ref "R9") (pin "2") (pinfunction "2_2") (pintype "passive"))
    )
    (net (code "24") (name "Net-(P1-Signal)") (class "Default")
      (node (ref "P1") (pin "1") (pinfunction "Signal_1") (pintype "input"))
      (node (ref "R10") (pin "1") (pinfunction "A_1") (pintype "passive"))
    )
    (net (code "25") (name "Net-(R8-A)") (class "Default")
      (node (ref "R8") (pin "1") (pinfunction "A_1") (pintype "passive"))
      (node (ref "R9") (pin "1") (pinfunction "A_1") (pintype "passive"))
      (node (ref "U3") (pin "3") (pinfunction "IN+_3") (pintype "input"))
    )
    (net (code "26") (name "Net-(U1A-ALARM)") (class "Default")
      (node (ref "RN2") (pin "3") (pinfunction "3_3") (pintype "passive"))
      (node (ref "U1") (pin "19") (pinfunction "ALARM_19") (pintype "passive"))
    )
    (net (code "27") (name "Net-(U1A-CLR)") (class "Default")
      (node (ref "RN2") (pin "4") (pinfunction "4_4") (pintype "passive"))
      (node (ref "U1") (pin "30") (pinfunction "CLR_30") (pintype "passive"))
    )
    (net (code "28") (name "Net-(U1A-LDAC)") (class "Default")
      (node (ref "RN2") (pin "2") (pinfunction "2_2") (pintype "passive"))
      (node (ref "U1") (pin "18") (pinfunction "LDAC_18") (pintype "passive"))
    )
    (net (code "29") (name "Net-(U1A-OUT)") (class "Default")
      (node (ref "U1") (pin "7") (pinfunction "OUT_7") (pintype "output"))
      (node (ref "U4") (pin "3") (pinfunction "IN+_3") (pintype "input"))
    )
    (net (code "30") (name "Net-(U1A-RCM)") (class "Default")
      (node (ref "U1") (pin "11") (pinfunction "RCM_11") (pintype "passive"))
      (node (ref "U6") (pin "2") (pinfunction "IN-_2") (pintype "input"))
    )
    (net (code "31") (name "Net-(U1A-REFNF)") (class "Default")
      (node (ref "C43") (pin "1") (pinfunction "1_1") (pintype "passive"))
      (node (ref "U1") (pin "5") (pinfunction "REFNF_5") (pintype "passive"))
      (node (ref "U5") (pin "6") (pinfunction "OUT_6") (pintype "output"))
    )
    (net (code "32") (name "Net-(U1A-REFNS)") (class "Default")
      (node (ref "C43") (pin "2") (pinfunction "2_2") (pintype "passive"))
      (node (ref "U1") (pin "6") (pinfunction "REFNS_6") (pintype "passive"))
      (node (ref "U5") (pin "2") (pinfunction "IN-_2") (pintype "input"))
    )
    (net (code "33") (name "Net-(U1A-REFPF)") (class "Default")
      (node (ref "C39") (pin "2") (pinfunction "2_2") (pintype "passive"))
      (node (ref "U1") (pin "3") (pinfunction "REFPF_3") (pintype "passive"))
      (node (ref "U2") (pin "6") (pinfunction "OUT_6") (pintype "output"))
    )
    (net (code "34") (name "Net-(U1A-REFPS)") (class "Default")
      (node (ref "C39") (pin "1") (pinfunction "1_1") (pintype "passive"))
      (node (ref "U1") (pin "4") (pinfunction "REFPS_4") (pintype "passive"))
      (node (ref "U2") (pin "2") (pinfunction "IN-_2") (pintype "input"))
    )
    (net (code "35") (name "Net-(U1A-RFB)") (class "Default")
      (node (ref "U1") (pin "9") (pinfunction "RFB_9") (pintype "passive"))
      (node (ref "U5") (pin "3") (pinfunction "IN+_3") (pintype "input"))
      (node (ref "U6") (pin "6") (pinfunction "OUT_6") (pintype "output"))
    )
    (net (code "36") (name "Net-(U1A-ROFS)") (class "Default")
      (node (ref "U1") (pin "10") (pinfunction "ROFS_10") (pintype "passive"))
      (node (ref "U2") (pin "3") (pinfunction "IN+_3") (pintype "input"))
      (node (ref "U3") (pin "2") (pinfunction "IN-_2") (pintype "input"))
      (node (ref "U3") (pin "6") (pinfunction "OUT_6") (pintype "output"))
    )
    (net (code "37") (name "Net-(U1A-SCLK)") (class "Default")
      (node (ref "RN1") (pin "1") (pinfunction "1_1") (pintype "passive"))
      (node (ref "U1") (pin "31") (pinfunction "SCLK_31") (pintype "passive"))
    )
    (net (code "38") (name "Net-(U1A-SDIN)") (class "Default")
      (node (ref "RN1") (pin "2") (pinfunction "2_2") (pintype "passive"))
      (node (ref "U1") (pin "32") (pinfunction "SDIN_32") (pintype "passive"))
    )
    (net (code "39") (name "Net-(U1A-SDO)") (class "Default")
      (node (ref "RN1") (pin "4") (pinfunction "4_4") (pintype "passive"))
      (node (ref "U1") (pin "34") (pinfunction "SDO_34") (pintype "passive"))
    )
    (net (code "40") (name "Net-(U1A-SYNC)") (class "Default")
      (node (ref "RN1") (pin "3") (pinfunction "3_3") (pintype "passive"))
      (node (ref "U1") (pin "33") (pinfunction "SYNC_33") (pintype "passive"))
    )
    (net (code "41") (name "Net-(U4A-IN-)") (class "Default")
      (node (ref "R10") (pin "2") (pinfunction "2_2") (pintype "passive"))
      (node (ref "R13") (pin "2") (pinfunction "2_2") (pintype "passive"))
      (node (ref "U4") (pin "2") (pinfunction "IN-_2") (pintype "input"))
      (node (ref "U4") (pin "6") (pinfunction "OUT_6") (pintype "output"))
    )
    (net (code "42") (name "Net-(U7A-IN-)") (class "Default")
      (node (ref "R14") (pin "3") (pinfunction "3_3") (pintype "passive"))
      (node (ref "U7") (pin "2") (pinfunction "IN-_2") (pintype "input"))
    )
    (net (code "43") (name "V_ref_pull") (class "Default")
      (node (ref "R14") (pin "1") (pinfunction "1_1") (pintype "passive"))
      (node (ref "R6") (pin "1") (pinfunction "A_1") (pintype "passive"))
      (node (ref "R7") (pin "1") (pinfunction "A_1") (pintype "passive"))
      (node (ref "U7") (pin "6") (pinfunction "OUT_6") (pintype "output"))
    )
    (net (code "44") (name "unconnected-(P3-Pad1)") (class "Default")
      (node (ref "P3") (pin "1") (pinfunction "1_1") (pintype "passive"))
    )
    (net (code "45") (name "unconnected-(P3-Pad2)") (class "Default")
      (node (ref "P3") (pin "2") (pinfunction "2_2") (pintype "passive"))
    )
    (net (code "46") (name "unconnected-(P3-Pad3)") (class "Default")
      (node (ref "P3") (pin "3") (pinfunction "3_3") (pintype "passive"))
    )
    (net (code "47") (name "unconnected-(P3-Pad4)") (class "Default")
      (node (ref "P3") (pin "4") (pinfunction "4_4") (pintype "passive"))
    )
    (net (code "48") (name "unconnected-(P3-Pad5)") (class "Default")
      (node (ref "P3") (pin "5") (pinfunction "5_5") (pintype "passive"))
    )
    (net (code "49") (name "unconnected-(P3-Pad6)") (class "Default")
      (node (ref "P3") (pin "6") (pinfunction "6_6") (pintype "passive"))
    )
    (net (code "50") (name "unconnected-(P3-Pad7)") (class "Default")
      (node (ref "P3") (pin "7") (pinfunction "7_7") (pintype "passive"))
    )
    (net (code "51") (name "unconnected-(P3-Pad8)") (class "Default")
      (node (ref "P3") (pin "8") (pinfunction "8_8") (pintype "passive"))
    )
    (net (code "52") (name "unconnected-(P3-Pad9)") (class "Default")
      (node (ref "P3") (pin "9") (pinfunction "9_9") (pintype "passive"))
    )
    (net (code "53") (name "unconnected-(P3-Pad10)") (class "Default")
      (node (ref "P3") (pin "10") (pinfunction "10_10") (pintype "passive"))
    )
    (net (code "54") (name "unconnected-(P3-Pad11)") (class "Default")
      (node (ref "P3") (pin "11") (pinfunction "11_11") (pintype "passive"))
    )
    (net (code "55") (name "unconnected-(P3-Pad12)") (class "Default")
      (node (ref "P3") (pin "12") (pinfunction "12_12") (pintype "passive"))
    )
    (net (code "56") (name "unconnected-(P3-Pad13)") (class "Default")
      (node (ref "P3") (pin "13") (pinfunction "13_13") (pintype "passive"))
    )
    (net (code "57") (name "unconnected-(P3-Pad14)") (class "Default")
      (node (ref "P3") (pin "14") (pinfunction "14_14") (pintype "passive"))
    )
    (net (code "58") (name "unconnected-(P3-Pad15)") (class "Default")
      (node (ref "P3") (pin "15") (pinfunction "15_15") (pintype "passive"))
    )
    (net (code "59") (name "unconnected-(P3-Pad16)") (class "Default")
      (node (ref "P3") (pin "16") (pinfunction "16_16") (pintype "passive"))
    )
    (net (code "60") (name "unconnected-(P3-Pad17)") (class "Default")
      (node (ref "P3") (pin "17") (pinfunction "17_17") (pintype "passive"))
    )
    (net (code "61") (name "unconnected-(P3-Pad18)") (class "Default")
      (node (ref "P3") (pin "18") (pinfunction "18_18") (pintype "passive"))
    )
    (net (code "62") (name "unconnected-(P3-Pad19)") (class "Default")
      (node (ref "P3") (pin "19") (pinfunction "19_19") (pintype "passive"))
    )
    (net (code "63") (name "unconnected-(P3-Pad20)") (class "Default")
      (node (ref "P3") (pin "20") (pinfunction "20_20") (pintype "passive"))
    )
    (net (code "64") (name "unconnected-(P3-Pad21)") (class "Default")
      (node (ref "P3") (pin "21") (pinfunction "21_21") (pintype "passive"))
    )
    (net (code "65") (name "unconnected-(P3-Pad22)") (class "Default")
      (node (ref "P3") (pin "22") (pinfunction "22_22") (pintype "passive"))
    )
    (net (code "66") (name "unconnected-(P3-Pad23)") (class "Default")
      (node (ref "P3") (pin "23") (pinfunction "23_23") (pintype "passive"))
    )
    (net (code "67") (name "unconnected-(P3-Pad24)") (class "Default")
      (node (ref "P3") (pin "24") (pinfunction "24_24") (pintype "passive"))
    )
    (net (code "68") (name "unconnected-(P3-Pad25)") (class "Default")
      (node (ref "P3") (pin "25") (pinfunction "25_25") (pintype "passive"))
    )
    (net (code "69") (name "unconnected-(P3-Pad26)") (class "Default")
      (node (ref "P3") (pin "26") (pinfunction "26_26") (pintype "passive"))
    )
    (net (code "70") (name "unconnected-(P3-Pad27)") (class "Default")
      (node (ref "P3") (pin "27") (pinfunction "27_27") (pintype "passive"))
    )
    (net (code "71") (name "unconnected-(P3-Pad28)") (class "Default")
      (node (ref "P3") (pin "28") (pinfunction "28_28") (pintype "passive"))
    )
    (net (code "72") (name "unconnected-(P3-Pad29)") (class "Default")
      (node (ref "P3") (pin "29") (pinfunction "29_29") (pintype "passive"))
    )
    (net (code "73") (name "unconnected-(P3-Pad30)") (class "Default")
      (node (ref "P3") (pin "30") (pinfunction "30_30") (pintype "passive"))
    )
    (net (code "74") (name "unconnected-(P3-Pad31)") (class "Default")
      (node (ref "P3") (pin "31") (pinfunction "31_31") (pintype "passive"))
    )
    (net (code "75") (name "unconnected-(P3-Pad32)") (class "Default")
      (node (ref "P3") (pin "32") (pinfunction "32_32") (pintype "passive"))
    )
    (net (code "76") (name "unconnected-(P3-Pad33)") (class "Default")
      (node (ref "P3") (pin "33") (pinfunction "33_33") (pintype "passive"))
    )
    (net (code "77") (name "unconnected-(P3-Pad34)") (class "Default")
      (node (ref "P3") (pin "34") (pinfunction "34_34") (pintype "passive"))
    )
    (net (code "78") (name "unconnected-(P3-Pad35)") (class "Default")
      (node (ref "P3") (pin "35") (pinfunction "35_35") (pintype "passive"))
    )
    (net (code "79") (name "unconnected-(P3-Pad36)") (class "Default")
      (node (ref "P3") (pin "36") (pinfunction "36_36") (pintype "passive"))
    )
    (net (code "80") (name "unconnected-(RN2-Pad1)") (class "Default")
      (node (ref "RN2") (pin "1") (pinfunction "1_1") (pintype "passive"))
    )
    (net (code "81") (name "unconnected-(RN2-Pad5)") (class "Default")
      (node (ref "RN2") (pin "5") (pinfunction "5_5") (pintype "passive"))
    )
  )
)
